# moisture-meter.net
KiCad netlist of a schematic drawn in EAGLE
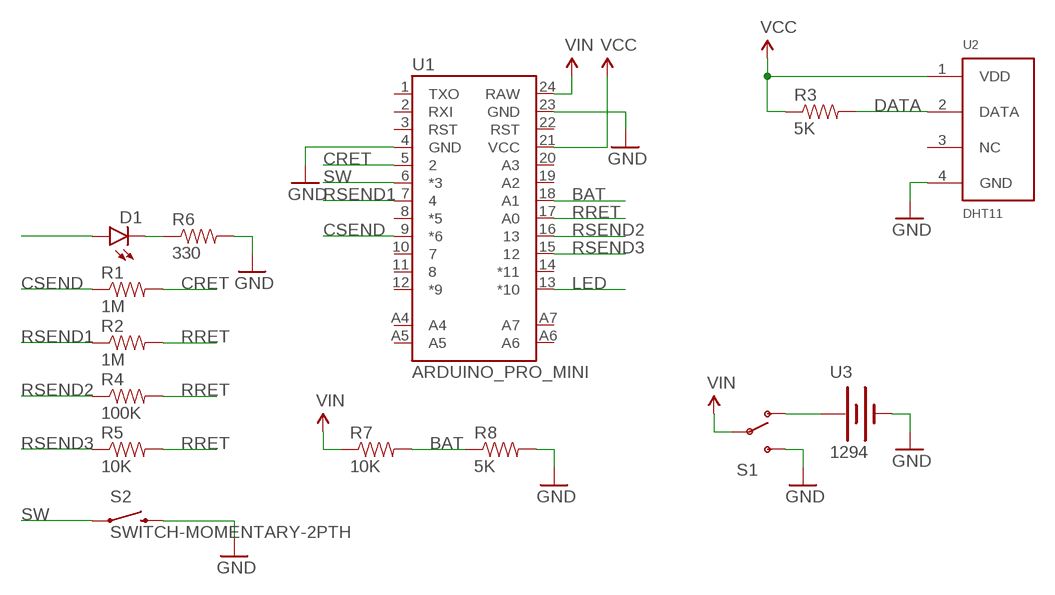
[diagram p0: schematic, sheet 1]

(export (version "E")
  (design (tool "Eeschema 10.0.6"))
  (components
    (comp (ref "D1")
      (value "LED5MM")
      (footprint "eagle-import:LED5MM")
      (libsource (lib "eagle-import") (part "LED5MM"))
    )
    (comp (ref "R1")
      (value "1M")
      (footprint "eagle-import:AXIAL-0.4")
      (libsource (lib "eagle-import") (part "RESISTORPTH-1/4W"))
    )
    (comp (ref "R2")
      (value "1M")
      (footprint "eagle-import:AXIAL-0.4")
      (libsource (lib "eagle-import") (part "RESISTORPTH-1/4W"))
    )
    (comp (ref "R3")
      (value "5K")
      (footprint "eagle-import:AXIAL-0.4")
      (libsource (lib "eagle-import") (part "RESISTORPTH-1/4W"))
    )
    (comp (ref "R4")
      (value "100K")
      (footprint "eagle-import:AXIAL-0.4")
      (libsource (lib "eagle-import") (part "RESISTORPTH-1/4W"))
    )
    (comp (ref "R5")
      (value "10K")
      (footprint "eagle-import:AXIAL-0.4")
      (libsource (lib "eagle-import") (part "RESISTORPTH-1/4W"))
    )
    (comp (ref "R6")
      (value "330")
      (footprint "eagle-import:AXIAL-0.4")
      (libsource (lib "eagle-import") (part "RESISTORPTH-1/4W"))
    )
    (comp (ref "R7")
      (value "10K")
      (footprint "eagle-import:AXIAL-0.4")
      (libsource (lib "eagle-import") (part "RESISTORPTH-1/4W"))
    )
    (comp (ref "R8")
      (value "5K")
      (footprint "eagle-import:AXIAL-0.4")
      (libsource (lib "eagle-import") (part "RESISTORPTH-1/4W"))
    )
    (comp (ref "S1")
      (value "SWITCH-SPDTPTH")
      (footprint "eagle-import:SWITCH-SPDT")
      (libsource (lib "eagle-import") (part "SWITCH-SPDTPTH"))
    )
    (comp (ref "S2")
      (value "SWITCH-MOMENTARY-2PTH")
      (footprint "eagle-import:TACTILE-PTH")
      (libsource (lib "eagle-import") (part "SWITCH-MOMENTARY-2PTH"))
    )
    (comp (ref "U1")
      (value "ARDUINO_PRO_MINI")
      (footprint "eagle-import:ARDUINO_PRO_MINI")
      (libsource (lib "eagle-import") (part "ARDUINO_PRO_MINI"))
    )
    (comp (ref "U2")
      (value "DHT11")
      (footprint "eagle-import:DHT11")
      (libsource (lib "eagle-import") (part "DHT11"))
    )
    (comp (ref "U3")
      (value "1294")
      (footprint "eagle-import:1294")
      (libsource (lib "eagle-import") (part "1294"))
    )
  )
  (nets
    (net (code "1") (name "/BAT") (class "Default")
      (node (ref "R7") (pin "P$2") (pinfunction "2_P$2") (pintype "passive"))
      (node (ref "R8") (pin "P$1") (pinfunction "1_P$1") (pintype "passive"))
      (node (ref "U1") (pin "18") (pinfunction "A1_18") (pintype "bidirectional"))
    )
    (net (code "2") (name "/CRET") (class "Default")
      (node (ref "R1") (pin "P$2") (pinfunction "2_P$2") (pintype "passive"))
      (node (ref "U1") (pin "5") (pinfunction "2_5") (pintype "bidirectional"))
    )
    (net (code "3") (name "/CSEND") (class "Default")
      (node (ref "R1") (pin "P$1") (pinfunction "1_P$1") (pintype "passive"))
      (node (ref "U1") (pin "9") (pinfunction "*6_9") (pintype "bidirectional"))
    )
    (net (code "4") (name "/DATA") (class "Default")
      (node (ref "R3") (pin "P$2") (pinfunction "2_P$2") (pintype "passive"))
      (node (ref "U2") (pin "2") (pinfunction "DATA_2") (pintype "bidirectional"))
    )
    (net (code "5") (name "/LED") (class "Default")
      (node (ref "D1") (pin "A") (pinfunction "A_A") (pintype "passive"))
      (node (ref "U1") (pin "13") (pinfunction "*10_13") (pintype "bidirectional"))
    )
    (net (code "6") (name "/RRET") (class "Default")
      (node (ref "R2") (pin "P$2") (pinfunction "2_P$2") (pintype "passive"))
      (node (ref "R4") (pin "P$2") (pinfunction "2_P$2") (pintype "passive"))
      (node (ref "R5") (pin "P$2") (pinfunction "2_P$2") (pintype "passive"))
      (node (ref "U1") (pin "17") (pinfunction "A0_17") (pintype "bidirectional"))
    )
    (net (code "7") (name "/RSEND1") (class "Default")
      (node (ref "R2") (pin "P$1") (pinfunction "1_P$1") (pintype "passive"))
      (node (ref "U1") (pin "7") (pinfunction "4_7") (pintype "bidirectional"))
    )
    (net (code "8") (name "/RSEND2") (class "Default")
      (node (ref "R4") (pin "P$1") (pinfunction "1_P$1") (pintype "passive"))
      (node (ref "U1") (pin "16") (pinfunction "13_16") (pintype "bidirectional"))
    )
    (net (code "9") (name "/RSEND3") (class "Default")
      (node (ref "R5") (pin "P$1") (pinfunction "1_P$1") (pintype "passive"))
      (node (ref "U1") (pin "15") (pinfunction "12_15") (pintype "bidirectional"))
    )
    (net (code "10") (name "/SW") (class "Default")
      (node (ref "S2") (pin "1") (pinfunction "1_1") (pintype "passive"))
      (node (ref "U1") (pin "6") (pinfunction "*3_6") (pintype "bidirectional"))
    )
    (net (code "11") (name "GND") (class "Default")
      (node (ref "R6") (pin "P$2") (pinfunction "2_P$2") (pintype "passive"))
      (node (ref "R8") (pin "P$2") (pinfunction "2_P$2") (pintype "passive"))
      (node (ref "S1") (pin "3") (pinfunction "S_3") (pintype "passive"))
      (node (ref "S2") (pin "3") (pinfunction "2_3") (pintype "passive"))
      (node (ref "U1") (pin "23") (pinfunction "GND_23") (pintype "bidirectional"))
      (node (ref "U1") (pin "4") (pinfunction "GND_4") (pintype "bidirectional"))
      (node (ref "U2") (pin "4") (pinfunction "GND_4") (pintype "power_in"))
      (node (ref "U3") (pin "-") (pinfunction "-_-") (pintype "power_in"))
    )
    (net (code "12") (name "Net-(D1-C)") (class "Default")
      (node (ref "D1") (pin "K") (pinfunction "C_K") (pintype "passive"))
      (node (ref "R6") (pin "P$1") (pinfunction "1_P$1") (pintype "passive"))
    )
    (net (code "13") (name "Net-(S1-O)") (class "Default")
      (node (ref "S1") (pin "1") (pinfunction "O_1") (pintype "passive"))
      (node (ref "U3") (pin "+") (pinfunction "+_+") (pintype "power_in"))
    )
    (net (code "14") (name "VCC") (class "Default")
      (node (ref "R3") (pin "P$1") (pinfunction "1_P$1") (pintype "passive"))
      (node (ref "U1") (pin "21") (pinfunction "VCC_21") (pintype "bidirectional"))
      (node (ref "U2") (pin "1") (pinfunction "VDD_1") (pintype "power_in"))
    )
    (net (code "15") (name "VIN") (class "Default")
      (node (ref "R7") (pin "P$1") (pinfunction "1_P$1") (pintype "passive"))
      (node (ref "S1") (pin "2") (pinfunction "P_2") (pintype "passive"))
      (node (ref "U1") (pin "24") (pinfunction "RAW_24") (pintype "bidirectional"))
    )
    (net (code "16") (name "unconnected-(U1-*5-Pad8)") (class "Default")
      (node (ref "U1") (pin "8") (pinfunction "*5_8") (pintype "bidirectional"))
    )
    (net (code "17") (name "unconnected-(U1-*9-Pad12)") (class "Default")
      (node (ref "U1") (pin "12") (pinfunction "*9_12") (pintype "bidirectional"))
    )
    (net (code "18") (name "unconnected-(U1-*11-Pad14)") (class "Default")
      (node (ref "U1") (pin "14") (pinfunction "*11_14") (pintype "bidirectional"))
    )
    (net (code "19") (name "unconnected-(U1-7-Pad10)") (class "Default")
      (node (ref "U1") (pin "10") (pinfunction "7_10") (pintype "bidirectional"))
    )
    (net (code "20") (name "unconnected-(U1-8-Pad11)") (class "Default")
      (node (ref "U1") (pin "11") (pinfunction "8_11") (pintype "bidirectional"))
    )
    (net (code "21") (name "unconnected-(U1-A2-Pad19)") (class "Default")
      (node (ref "U1") (pin "19") (pinfunction "A2_19") (pintype "bidirectional"))
    )
    (net (code "22") (name "unconnected-(U1-A3-Pad20)") (class "Default")
      (node (ref "U1") (pin "20") (pinfunction "A3_20") (pintype "bidirectional"))
    )
    (net (code "23") (name "unconnected-(U1-PadA4)") (class "Default")
      (node (ref "U1") (pin "A4") (pinfunction "A4_A4") (pintype "bidirectional"))
    )
    (net (code "24") (name "unconnected-(U1-PadA5)") (class "Default")
      (node (ref "U1") (pin "A5") (pinfunction "A5_A5") (pintype "bidirectional"))
    )
    (net (code "25") (name "unconnected-(U1-PadA6)") (class "Default")
      (node (ref "U1") (pin "A6") (pinfunction "A6_A6") (pintype "bidirectional"))
    )
    (net (code "26") (name "unconnected-(U1-PadA7)") (class "Default")
      (node (ref "U1") (pin "A7") (pinfunction "A7_A7") (pintype "bidirectional"))
    )
    (net (code "27") (name "unconnected-(U1-RST-Pad3)") (class "Default")
      (node (ref "U1") (pin "3") (pinfunction "RST_3") (pintype "bidirectional"))
    )
    (net (code "28") (name "unconnected-(U1-RST-Pad22)") (class "Default")
      (node (ref "U1") (pin "22") (pinfunction "RST_22") (pintype "bidirectional"))
    )
    (net (code "29") (name "unconnected-(U1-RXI-Pad2)") (class "Default")
      (node (ref "U1") (pin "2") (pinfunction "RXI_2") (pintype "bidirectional"))
    )
    (net (code "30") (name "unconnected-(U1-TXO-Pad1)") (class "Default")
      (node (ref "U1") (pin "1") (pinfunction "TXO_1") (pintype "bidirectional"))
    )
    (net (code "31") (name "unconnected-(U2-NC-Pad3)") (class "Default")
      (node (ref "U2") (pin "3") (pinfunction "NC_3") (pintype "bidirectional"))
    )
  )
)
